# ProPrj_Motorcycle_Controller_2026-08-27_.net
KiCad netlist of a schematic drawn in EasyEDA Pro
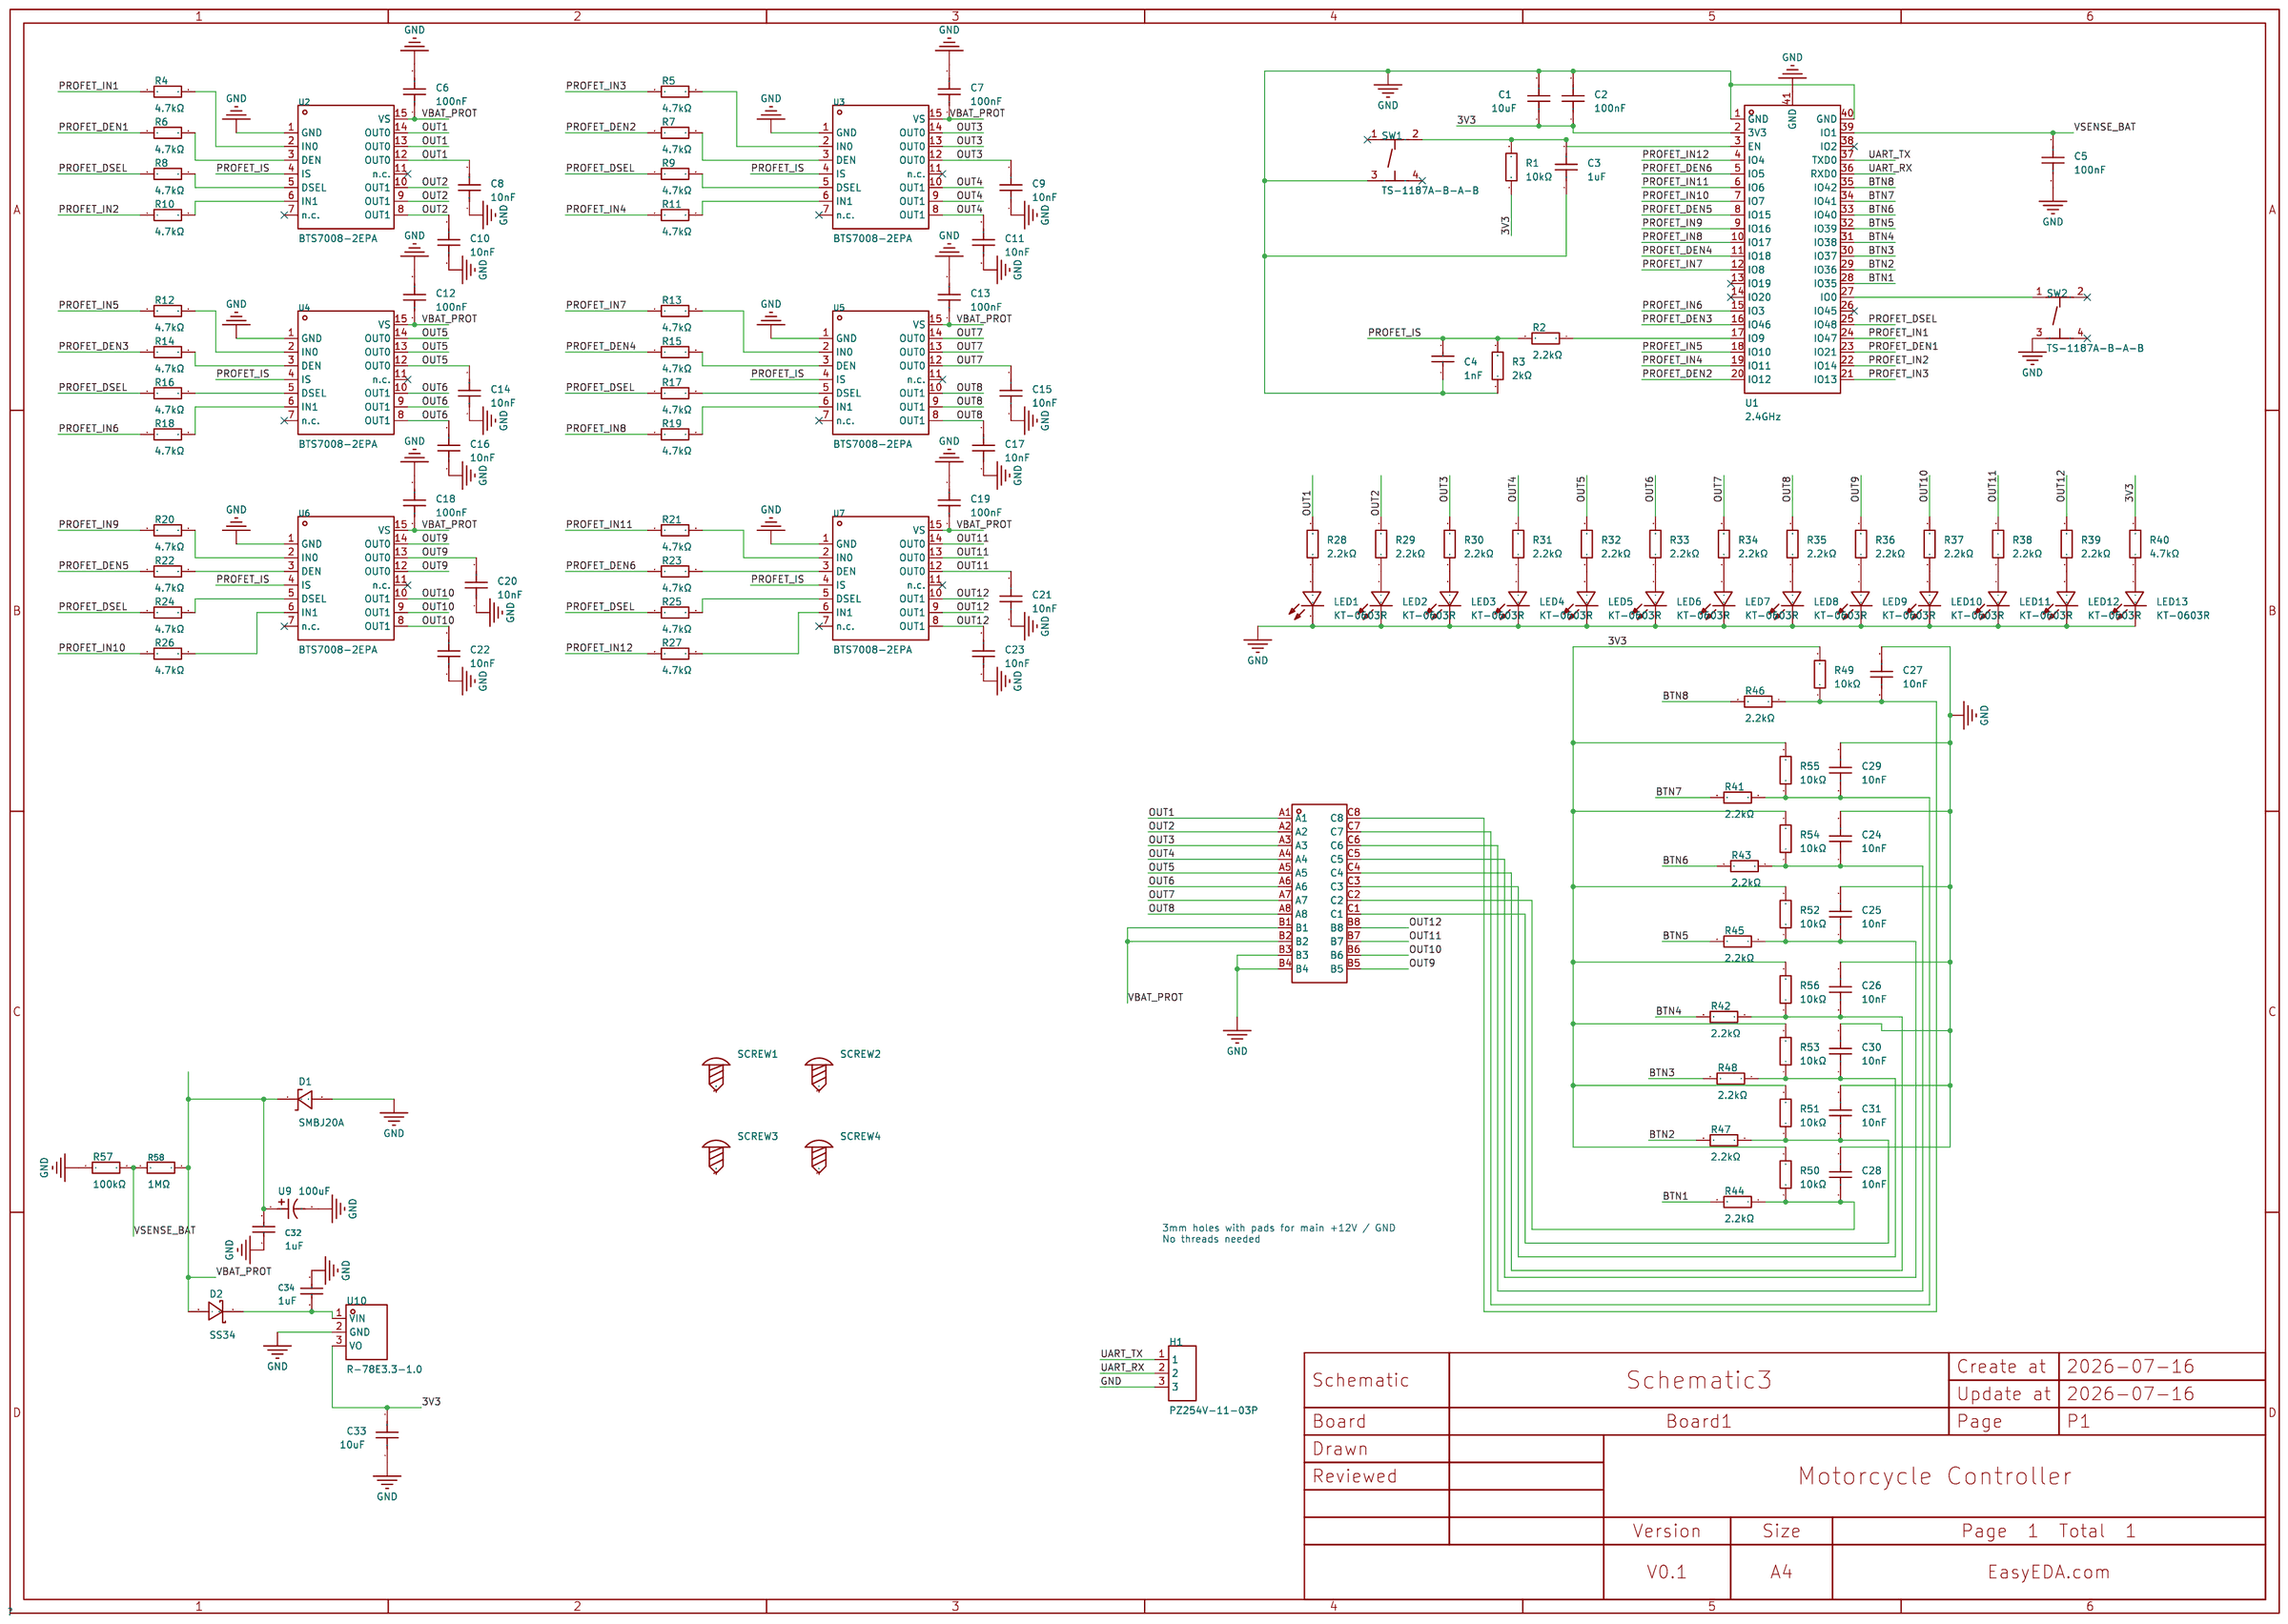
[diagram p0: schematic sheet]

(export (version "E")
  (design (tool "Eeschema 10.0.6"))
  (components
    (comp (ref "C1")
      (value "10uF")
      (footprint "easyedapro:C0603")
      (fields
        (field (name "Manufacturer Part") "CL10A106KP8NNNC")
        (field (name "Manufacturer") "SAMSUNG(三星)")
      )
      (libsource (lib "easyedapro") (part "CL10A106KP8NNNC"))
    )
    (comp (ref "C2")
      (value "100nF")
      (footprint "easyedapro:C0402")
      (fields
        (field (name "Manufacturer Part") "CL05B104KO5NNNC")
        (field (name "Manufacturer") "SAMSUNG(三星)")
      )
      (libsource (lib "easyedapro") (part "CL05B104KO5NNNC"))
    )
    (comp (ref "C3")
      (value "1uF")
      (footprint "easyedapro:C0402")
      (fields
        (field (name "Manufacturer Part") "CL05A105KA5NQNC")
        (field (name "Manufacturer") "SAMSUNG(三星)")
      )
      (libsource (lib "easyedapro") (part "CL05A105KA5NQNC"))
    )
    (comp (ref "C4")
      (value "1nF")
      (footprint "easyedapro:C0402")
      (fields (field (name "Manufacturer Part") "0402B102K500NT") (field (name "Manufacturer") "FH(风华)"))
      (libsource (lib "easyedapro") (part "0402B102K500NT"))
    )
    (comp (ref "C5")
      (value "100nF")
      (footprint "easyedapro:C0402")
      (fields
        (field (name "Manufacturer Part") "CL05B104KO5NNNC")
        (field (name "Manufacturer") "SAMSUNG(三星)")
      )
      (libsource (lib "easyedapro") (part "CL05B104KO5NNNC"))
    )
    (comp (ref "C6")
      (value "100nF")
      (footprint "easyedapro:C0603")
      (fields
        (field (name "Manufacturer Part") "CC0603KRX7R9BB104")
        (field (name "Manufacturer") "YAGEO(国巨)")
      )
      (libsource (lib "easyedapro") (part "CC0603KRX7R9BB104"))
    )
    (comp (ref "C7")
      (value "100nF")
      (footprint "easyedapro:C0603")
      (fields
        (field (name "Manufacturer Part") "CC0603KRX7R9BB104")
        (field (name "Manufacturer") "YAGEO(国巨)")
      )
      (libsource (lib "easyedapro") (part "CC0603KRX7R9BB104"))
    )
    (comp (ref "C8")
      (value "10nF")
      (footprint "easyedapro:C0603")
      (fields (field (name "Manufacturer Part") "0603B103K500NT") (field (name "Manufacturer") "FH(风华)"))
      (libsource (lib "easyedapro") (part "0603B103K500NT"))
    )
    (comp (ref "C9")
      (value "10nF")
      (footprint "easyedapro:C0603")
      (fields (field (name "Manufacturer Part") "0603B103K500NT") (field (name "Manufacturer") "FH(风华)"))
      (libsource (lib "easyedapro") (part "0603B103K500NT"))
    )
    (comp (ref "C10")
      (value "10nF")
      (footprint "easyedapro:C0603")
      (fields (field (name "Manufacturer Part") "0603B103K500NT") (field (name "Manufacturer") "FH(风华)"))
      (libsource (lib "easyedapro") (part "0603B103K500NT"))
    )
    (comp (ref "C11")
      (value "10nF")
      (footprint "easyedapro:C0603")
      (fields (field (name "Manufacturer Part") "0603B103K500NT") (field (name "Manufacturer") "FH(风华)"))
      (libsource (lib "easyedapro") (part "0603B103K500NT"))
    )
    (comp (ref "C12")
      (value "100nF")
      (footprint "easyedapro:C0603")
      (fields
        (field (name "Manufacturer Part") "CC0603KRX7R9BB104")
        (field (name "Manufacturer") "YAGEO(国巨)")
      )
      (libsource (lib "easyedapro") (part "CC0603KRX7R9BB104"))
    )
    (comp (ref "C13")
      (value "100nF")
      (footprint "easyedapro:C0603")
      (fields
        (field (name "Manufacturer Part") "CC0603KRX7R9BB104")
        (field (name "Manufacturer") "YAGEO(国巨)")
      )
      (libsource (lib "easyedapro") (part "CC0603KRX7R9BB104"))
    )
    (comp (ref "C14")
      (value "10nF")
      (footprint "easyedapro:C0603")
      (fields (field (name "Manufacturer Part") "0603B103K500NT") (field (name "Manufacturer") "FH(风华)"))
      (libsource (lib "easyedapro") (part "0603B103K500NT"))
    )
    (comp (ref "C15")
      (value "10nF")
      (footprint "easyedapro:C0603")
      (fields (field (name "Manufacturer Part") "0603B103K500NT") (field (name "Manufacturer") "FH(风华)"))
      (libsource (lib "easyedapro") (part "0603B103K500NT"))
    )
    (comp (ref "C16")
      (value "10nF")
      (footprint "easyedapro:C0603")
      (fields (field (name "Manufacturer Part") "0603B103K500NT") (field (name "Manufacturer") "FH(风华)"))
      (libsource (lib "easyedapro") (part "0603B103K500NT"))
    )
    (comp (ref "C17")
      (value "10nF")
      (footprint "easyedapro:C0603")
      (fields (field (name "Manufacturer Part") "0603B103K500NT") (field (name "Manufacturer") "FH(风华)"))
      (libsource (lib "easyedapro") (part "0603B103K500NT"))
    )
    (comp (ref "C18")
      (value "100nF")
      (footprint "easyedapro:C0603")
      (fields
        (field (name "Manufacturer Part") "CC0603KRX7R9BB104")
        (field (name "Manufacturer") "YAGEO(国巨)")
      )
      (libsource (lib "easyedapro") (part "CC0603KRX7R9BB104"))
    )
    (comp (ref "C19")
      (value "100nF")
      (footprint "easyedapro:C0603")
      (fields
        (field (name "Manufacturer Part") "CC0603KRX7R9BB104")
        (field (name "Manufacturer") "YAGEO(国巨)")
      )
      (libsource (lib "easyedapro") (part "CC0603KRX7R9BB104"))
    )
    (comp (ref "C20")
      (value "10nF")
      (footprint "easyedapro:C0603")
      (fields (field (name "Manufacturer Part") "0603B103K500NT") (field (name "Manufacturer") "FH(风华)"))
      (libsource (lib "easyedapro") (part "0603B103K500NT"))
    )
    (comp (ref "C21")
      (value "10nF")
      (footprint "easyedapro:C0603")
      (fields (field (name "Manufacturer Part") "0603B103K500NT") (field (name "Manufacturer") "FH(风华)"))
      (libsource (lib "easyedapro") (part "0603B103K500NT"))
    )
    (comp (ref "C22")
      (value "10nF")
      (footprint "easyedapro:C0603")
      (fields (field (name "Manufacturer Part") "0603B103K500NT") (field (name "Manufacturer") "FH(风华)"))
      (libsource (lib "easyedapro") (part "0603B103K500NT"))
    )
    (comp (ref "C23")
      (value "10nF")
      (footprint "easyedapro:C0603")
      (fields (field (name "Manufacturer Part") "0603B103K500NT") (field (name "Manufacturer") "FH(风华)"))
      (libsource (lib "easyedapro") (part "0603B103K500NT"))
    )
    (comp (ref "C24")
      (value "10nF")
      (footprint "easyedapro:C0603")
      (fields (field (name "Manufacturer Part") "0603B103K500NT") (field (name "Manufacturer") "FH(风华)"))
      (libsource (lib "easyedapro") (part "0603B103K500NT"))
    )
    (comp (ref "C25")
      (value "10nF")
      (footprint "easyedapro:C0603")
      (fields (field (name "Manufacturer Part") "0603B103K500NT") (field (name "Manufacturer") "FH(风华)"))
      (libsource (lib "easyedapro") (part "0603B103K500NT"))
    )
    (comp (ref "C26")
      (value "10nF")
      (footprint "easyedapro:C0603")
      (fields (field (name "Manufacturer Part") "0603B103K500NT") (field (name "Manufacturer") "FH(风华)"))
      (libsource (lib "easyedapro") (part "0603B103K500NT"))
    )
    (comp (ref "C27")
      (value "10nF")
      (footprint "easyedapro:C0603")
      (fields (field (name "Manufacturer Part") "0603B103K500NT") (field (name "Manufacturer") "FH(风华)"))
      (libsource (lib "easyedapro") (part "0603B103K500NT"))
    )
    (comp (ref "C28")
      (value "10nF")
      (footprint "easyedapro:C0603")
      (fields (field (name "Manufacturer Part") "0603B103K500NT") (field (name "Manufacturer") "FH(风华)"))
      (libsource (lib "easyedapro") (part "0603B103K500NT"))
    )
    (comp (ref "C29")
      (value "10nF")
      (footprint "easyedapro:C0603")
      (fields (field (name "Manufacturer Part") "0603B103K500NT") (field (name "Manufacturer") "FH(风华)"))
      (libsource (lib "easyedapro") (part "0603B103K500NT"))
    )
    (comp (ref "C30")
      (value "10nF")
      (footprint "easyedapro:C0603")
      (fields (field (name "Manufacturer Part") "0603B103K500NT") (field (name "Manufacturer") "FH(风华)"))
      (libsource (lib "easyedapro") (part "0603B103K500NT"))
    )
    (comp (ref "C31")
      (value "10nF")
      (footprint "easyedapro:C0603")
      (fields (field (name "Manufacturer Part") "0603B103K500NT") (field (name "Manufacturer") "FH(风华)"))
      (libsource (lib "easyedapro") (part "0603B103K500NT"))
    )
    (comp (ref "C32")
      (value "1uF")
      (footprint "easyedapro:C0805")
      (fields
        (field (name "Manufacturer Part") "CL21B105KBFNNNE")
        (field (name "Manufacturer") "SAMSUNG(三星)")
      )
      (libsource (lib "easyedapro") (part "CL21B105KBFNNNE"))
    )
    (comp (ref "C33")
      (value "10uF")
      (footprint "easyedapro:C0603")
      (fields
        (field (name "Manufacturer Part") "CL10A106KP8NNNC")
        (field (name "Manufacturer") "SAMSUNG(三星)")
      )
      (libsource (lib "easyedapro") (part "CL10A106KP8NNNC"))
    )
    (comp (ref "C34")
      (value "1uF")
      (footprint "easyedapro:C0805")
      (fields
        (field (name "Manufacturer Part") "CL21B105KBFNNNE")
        (field (name "Manufacturer") "SAMSUNG(三星)")
      )
      (libsource (lib "easyedapro") (part "CL21B105KBFNNNE"))
    )
    (comp (ref "CN3")
      (value "HCCPHPE24BKA90F")
      (footprint "easyedapro:CONN-TH_HCCPHPE24BKA90F")
      (fields (field (name "Manufacturer") "Aptiv(Delphi)"))
      (libsource (lib "easyedapro") (part "HCCPHPE24BKA90F_C5349068"))
    )
    (comp (ref "D1")
      (value "SMBJ20A")
      (footprint "easyedapro:SMB_L4.6-W3.6-LS5.3-RD")
      (fields (field (name "Manufacturer") "MDD(辰达半导体)"))
      (libsource (lib "easyedapro") (part "SMBJ20A_C364296"))
    )
    (comp (ref "D2")
      (value "SS34")
      (footprint "easyedapro:SMA_L4.3-W2.6-LS5.2-RD")
      (fields (field (name "Manufacturer") "MDD(辰达半导体)"))
      (libsource (lib "easyedapro") (part "SS34_C8678"))
    )
    (comp (ref "H1")
      (value "PZ254V-11-03P")
      (footprint "easyedapro:HDR-TH_3P-P2.54-V-M_PZ254V-11-03P")
      (fields (field (name "Manufacturer") "XFCN(兴飞)"))
      (libsource (lib "easyedapro") (part "PZ254V-11-03P_C2937625"))
    )
    (comp (ref "LED1")
      (value "KT-0603R")
      (footprint "easyedapro:LED-SMD_L1.6-W0.8-R-RD")
      (fields (field (name "Manufacturer") "KENTO"))
      (libsource (lib "easyedapro") (part "KT-0603R"))
    )
    (comp (ref "LED2")
      (value "KT-0603R")
      (footprint "easyedapro:LED-SMD_L1.6-W0.8-R-RD")
      (fields (field (name "Manufacturer") "KENTO"))
      (libsource (lib "easyedapro") (part "KT-0603R"))
    )
    (comp (ref "LED3")
      (value "KT-0603R")
      (footprint "easyedapro:LED-SMD_L1.6-W0.8-R-RD")
      (fields (field (name "Manufacturer") "KENTO"))
      (libsource (lib "easyedapro") (part "KT-0603R"))
    )
    (comp (ref "LED4")
      (value "KT-0603R")
      (footprint "easyedapro:LED-SMD_L1.6-W0.8-R-RD")
      (fields (field (name "Manufacturer") "KENTO"))
      (libsource (lib "easyedapro") (part "KT-0603R"))
    )
    (comp (ref "LED5")
      (value "KT-0603R")
      (footprint "easyedapro:LED-SMD_L1.6-W0.8-R-RD")
      (fields (field (name "Manufacturer") "KENTO"))
      (libsource (lib "easyedapro") (part "KT-0603R"))
    )
    (comp (ref "LED6")
      (value "KT-0603R")
      (footprint "easyedapro:LED-SMD_L1.6-W0.8-R-RD")
      (fields (field (name "Manufacturer") "KENTO"))
      (libsource (lib "easyedapro") (part "KT-0603R"))
    )
    (comp (ref "LED7")
      (value "KT-0603R")
      (footprint "easyedapro:LED-SMD_L1.6-W0.8-R-RD")
      (fields (field (name "Manufacturer") "KENTO"))
      (libsource (lib "easyedapro") (part "KT-0603R"))
    )
    (comp (ref "LED8")
      (value "KT-0603R")
      (footprint "easyedapro:LED-SMD_L1.6-W0.8-R-RD")
      (fields (field (name "Manufacturer") "KENTO"))
      (libsource (lib "easyedapro") (part "KT-0603R"))
    )
    (comp (ref "LED9")
      (value "KT-0603R")
      (footprint "easyedapro:LED-SMD_L1.6-W0.8-R-RD")
      (fields (field (name "Manufacturer") "KENTO"))
      (libsource (lib "easyedapro") (part "KT-0603R"))
    )
    (comp (ref "LED10")
      (value "KT-0603R")
      (footprint "easyedapro:LED-SMD_L1.6-W0.8-R-RD")
      (fields (field (name "Manufacturer") "KENTO"))
      (libsource (lib "easyedapro") (part "KT-0603R"))
    )
    (comp (ref "LED11")
      (value "KT-0603R")
      (footprint "easyedapro:LED-SMD_L1.6-W0.8-R-RD")
      (fields (field (name "Manufacturer") "KENTO"))
      (libsource (lib "easyedapro") (part "KT-0603R"))
    )
    (comp (ref "LED12")
      (value "KT-0603R")
      (footprint "easyedapro:LED-SMD_L1.6-W0.8-R-RD")
      (fields (field (name "Manufacturer") "KENTO"))
      (libsource (lib "easyedapro") (part "KT-0603R"))
    )
    (comp (ref "LED13")
      (value "KT-0603R")
      (footprint "easyedapro:LED-SMD_L1.6-W0.8-R-RD")
      (fields (field (name "Manufacturer") "KENTO"))
      (libsource (lib "easyedapro") (part "KT-0603R"))
    )
    (comp (ref "R1")
      (value "10kΩ")
      (footprint "easyedapro:R0402")
      (fields (field (name "Manufacturer Part") "RC0402FR-0710KL") (field (name "Manufacturer") "YAGEO(国巨)"))
      (libsource (lib "easyedapro") (part "RC0402FR-0710KL"))
    )
    (comp (ref "R2")
      (value "2.2kΩ")
      (footprint "easyedapro:R0603")
      (fields
        (field (name "Manufacturer Part") "0603WAF2201T5E")
        (field (name "Manufacturer") "UNI-ROYAL(厚声)")
      )
      (libsource (lib "easyedapro") (part "0603WAF2201T5E"))
    )
    (comp (ref "R3")
      (value "2kΩ")
      (footprint "easyedapro:R0603")
      (fields
        (field (name "Manufacturer Part") "0603WAF2001T5E")
        (field (name "Manufacturer") "UNI-ROYAL(厚声)")
      )
      (libsource (lib "easyedapro") (part "0603WAF2001T5E"))
    )
    (comp (ref "R4")
      (value "4.7kΩ")
      (footprint "easyedapro:R0603")
      (fields
        (field (name "Manufacturer Part") "0603WAF4701T5E")
        (field (name "Manufacturer") "UNI-ROYAL(厚声)")
      )
      (libsource (lib "easyedapro") (part "0603WAF4701T5E"))
    )
    (comp (ref "R5")
      (value "4.7kΩ")
      (footprint "easyedapro:R0603")
      (fields
        (field (name "Manufacturer Part") "0603WAF4701T5E")
        (field (name "Manufacturer") "UNI-ROYAL(厚声)")
      )
      (libsource (lib "easyedapro") (part "0603WAF4701T5E"))
    )
    (comp (ref "R6")
      (value "4.7kΩ")
      (footprint "easyedapro:R0603")
      (fields
        (field (name "Manufacturer Part") "0603WAF4701T5E")
        (field (name "Manufacturer") "UNI-ROYAL(厚声)")
      )
      (libsource (lib "easyedapro") (part "0603WAF4701T5E"))
    )
    (comp (ref "R7")
      (value "4.7kΩ")
      (footprint "easyedapro:R0603")
      (fields
        (field (name "Manufacturer Part") "0603WAF4701T5E")
        (field (name "Manufacturer") "UNI-ROYAL(厚声)")
      )
      (libsource (lib "easyedapro") (part "0603WAF4701T5E"))
    )
    (comp (ref "R8")
      (value "4.7kΩ")
      (footprint "easyedapro:R0603")
      (fields
        (field (name "Manufacturer Part") "0603WAF4701T5E")
        (field (name "Manufacturer") "UNI-ROYAL(厚声)")
      )
      (libsource (lib "easyedapro") (part "0603WAF4701T5E"))
    )
    (comp (ref "R9")
      (value "4.7kΩ")
      (footprint "easyedapro:R0603")
      (fields
        (field (name "Manufacturer Part") "0603WAF4701T5E")
        (field (name "Manufacturer") "UNI-ROYAL(厚声)")
      )
      (libsource (lib "easyedapro") (part "0603WAF4701T5E"))
    )
    (comp (ref "R10")
      (value "4.7kΩ")
      (footprint "easyedapro:R0603")
      (fields
        (field (name "Manufacturer Part") "0603WAF4701T5E")
        (field (name "Manufacturer") "UNI-ROYAL(厚声)")
      )
      (libsource (lib "easyedapro") (part "0603WAF4701T5E"))
    )
    (comp (ref "R11")
      (value "4.7kΩ")
      (footprint "easyedapro:R0603")
      (fields
        (field (name "Manufacturer Part") "0603WAF4701T5E")
        (field (name "Manufacturer") "UNI-ROYAL(厚声)")
      )
      (libsource (lib "easyedapro") (part "0603WAF4701T5E"))
    )
    (comp (ref "R12")
      (value "4.7kΩ")
      (footprint "easyedapro:R0603")
      (fields
        (field (name "Manufacturer Part") "0603WAF4701T5E")
        (field (name "Manufacturer") "UNI-ROYAL(厚声)")
      )
      (libsource (lib "easyedapro") (part "0603WAF4701T5E"))
    )
    (comp (ref "R13")
      (value "4.7kΩ")
      (footprint "easyedapro:R0603")
      (fields
        (field (name "Manufacturer Part") "0603WAF4701T5E")
        (field (name "Manufacturer") "UNI-ROYAL(厚声)")
      )
      (libsource (lib "easyedapro") (part "0603WAF4701T5E"))
    )
    (comp (ref "R14")
      (value "4.7kΩ")
      (footprint "easyedapro:R0603")
      (fields
        (field (name "Manufacturer Part") "0603WAF4701T5E")
        (field (name "Manufacturer") "UNI-ROYAL(厚声)")
      )
      (libsource (lib "easyedapro") (part "0603WAF4701T5E"))
    )
    (comp (ref "R15")
      (value "4.7kΩ")
      (footprint "easyedapro:R0603")
      (fields
        (field (name "Manufacturer Part") "0603WAF4701T5E")
        (field (name "Manufacturer") "UNI-ROYAL(厚声)")
      )
      (libsource (lib "easyedapro") (part "0603WAF4701T5E"))
    )
    (comp (ref "R16")
      (value "4.7kΩ")
      (footprint "easyedapro:R0603")
      (fields
        (field (name "Manufacturer Part") "0603WAF4701T5E")
        (field (name "Manufacturer") "UNI-ROYAL(厚声)")
      )
      (libsource (lib "easyedapro") (part "0603WAF4701T5E"))
    )
    (comp (ref "R17")
      (value "4.7kΩ")
      (footprint "easyedapro:R0603")
      (fields
        (field (name "Manufacturer Part") "0603WAF4701T5E")
        (field (name "Manufacturer") "UNI-ROYAL(厚声)")
      )
      (libsource (lib "easyedapro") (part "0603WAF4701T5E"))
    )
    (comp (ref "R18")
      (value "4.7kΩ")
      (footprint "easyedapro:R0603")
      (fields
        (field (name "Manufacturer Part") "0603WAF4701T5E")
        (field (name "Manufacturer") "UNI-ROYAL(厚声)")
      )
      (libsource (lib "easyedapro") (part "0603WAF4701T5E"))
    )
    (comp (ref "R19")
      (value "4.7kΩ")
      (footprint "easyedapro:R0603")
      (fields
        (field (name "Manufacturer Part") "0603WAF4701T5E")
        (field (name "Manufacturer") "UNI-ROYAL(厚声)")
      )
      (libsource (lib "easyedapro") (part "0603WAF4701T5E"))
    )
    (comp (ref "R20")
      (value "4.7kΩ")
      (footprint "easyedapro:R0603")
      (fields
        (field (name "Manufacturer Part") "0603WAF4701T5E")
        (field (name "Manufacturer") "UNI-ROYAL(厚声)")
      )
      (libsource (lib "easyedapro") (part "0603WAF4701T5E"))
    )
    (comp (ref "R21")
      (value "4.7kΩ")
      (footprint "easyedapro:R0603")
      (fields
        (field (name "Manufacturer Part") "0603WAF4701T5E")
        (field (name "Manufacturer") "UNI-ROYAL(厚声)")
      )
      (libsource (lib "easyedapro") (part "0603WAF4701T5E"))
    )
    (comp (ref "R22")
      (value "4.7kΩ")
      (footprint "easyedapro:R0603")
      (fields
        (field (name "Manufacturer Part") "0603WAF4701T5E")
        (field (name "Manufacturer") "UNI-ROYAL(厚声)")
      )
      (libsource (lib "easyedapro") (part "0603WAF4701T5E"))
    )
    (comp (ref "R23")
      (value "4.7kΩ")
      (footprint "easyedapro:R0603")
      (fields
        (field (name "Manufacturer Part") "0603WAF4701T5E")
        (field (name "Manufacturer") "UNI-ROYAL(厚声)")
      )
      (libsource (lib "easyedapro") (part "0603WAF4701T5E"))
    )
    (comp (ref "R24")
      (value "4.7kΩ")
      (footprint "easyedapro:R0603")
      (fields
        (field (name "Manufacturer Part") "0603WAF4701T5E")
        (field (name "Manufacturer") "UNI-ROYAL(厚声)")
      )
      (libsource (lib "easyedapro") (part "0603WAF4701T5E"))
    )
    (comp (ref "R25")
      (value "4.7kΩ")
      (footprint "easyedapro:R0603")
      (fields
        (field (name "Manufacturer Part") "0603WAF4701T5E")
        (field (name "Manufacturer") "UNI-ROYAL(厚声)")
      )
      (libsource (lib "easyedapro") (part "0603WAF4701T5E"))
    )
    (comp (ref "R26")
      (value "4.7kΩ")
      (footprint "easyedapro:R0603")
      (fields
        (field (name "Manufacturer Part") "0603WAF4701T5E")
        (field (name "Manufacturer") "UNI-ROYAL(厚声)")
      )
      (libsource (lib "easyedapro") (part "0603WAF4701T5E"))
    )
    (comp (ref "R27")
      (value "4.7kΩ")
      (footprint "easyedapro:R0603")
      (fields
        (field (name "Manufacturer Part") "0603WAF4701T5E")
        (field (name "Manufacturer") "UNI-ROYAL(厚声)")
      )
      (libsource (lib "easyedapro") (part "0603WAF4701T5E"))
    )
    (comp (ref "R28")
      (value "2.2kΩ")
      (footprint "easyedapro:R0603")
      (fields
        (field (name "Manufacturer Part") "0603WAF2201T5E")
        (field (name "Manufacturer") "UNI-ROYAL(厚声)")
      )
      (libsource (lib "easyedapro") (part "0603WAF2201T5E"))
    )
    (comp (ref "R29")
      (value "2.2kΩ")
      (footprint "easyedapro:R0603")
      (fields
        (field (name "Manufacturer Part") "0603WAF2201T5E")
        (field (name "Manufacturer") "UNI-ROYAL(厚声)")
      )
      (libsource (lib "easyedapro") (part "0603WAF2201T5E"))
    )
    (comp (ref "R30")
      (value "2.2kΩ")
      (footprint "easyedapro:R0603")
      (fields
        (field (name "Manufacturer Part") "0603WAF2201T5E")
        (field (name "Manufacturer") "UNI-ROYAL(厚声)")
      )
      (libsource (lib "easyedapro") (part "0603WAF2201T5E"))
    )
    (comp (ref "R31")
      (value "2.2kΩ")
      (footprint "easyedapro:R0603")
      (fields
        (field (name "Manufacturer Part") "0603WAF2201T5E")
        (field (name "Manufacturer") "UNI-ROYAL(厚声)")
      )
      (libsource (lib "easyedapro") (part "0603WAF2201T5E"))
    )
    (comp (ref "R32")
      (value "2.2kΩ")
      (footprint "easyedapro:R0603")
      (fields
        (field (name "Manufacturer Part") "0603WAF2201T5E")
        (field (name "Manufacturer") "UNI-ROYAL(厚声)")
      )
      (libsource (lib "easyedapro") (part "0603WAF2201T5E"))
    )
    (comp (ref "R33")
      (value "2.2kΩ")
      (footprint "easyedapro:R0603")
      (fields
        (field (name "Manufacturer Part") "0603WAF2201T5E")
        (field (name "Manufacturer") "UNI-ROYAL(厚声)")
      )
      (libsource (lib "easyedapro") (part "0603WAF2201T5E"))
    )
    (comp (ref "R34")
      (value "2.2kΩ")
      (footprint "easyedapro:R0603")
      (fields
        (field (name "Manufacturer Part") "0603WAF2201T5E")
        (field (name "Manufacturer") "UNI-ROYAL(厚声)")
      )
      (libsource (lib "easyedapro") (part "0603WAF2201T5E"))
    )
    (comp (ref "R35")
      (value "2.2kΩ")
      (footprint "easyedapro:R0603")
      (fields
        (field (name "Manufacturer Part") "0603WAF2201T5E")
        (field (name "Manufacturer") "UNI-ROYAL(厚声)")
      )
      (libsource (lib "easyedapro") (part "0603WAF2201T5E"))
    )
    (comp (ref "R36")
      (value "2.2kΩ")
      (footprint "easyedapro:R0603")
      (fields
        (field (name "Manufacturer Part") "0603WAF2201T5E")
        (field (name "Manufacturer") "UNI-ROYAL(厚声)")
      )
      (libsource (lib "easyedapro") (part "0603WAF2201T5E"))
    )
    (comp (ref "R37")
      (value "2.2kΩ")
      (footprint "easyedapro:R0603")
      (fields
        (field (name "Manufacturer Part") "0603WAF2201T5E")
        (field (name "Manufacturer") "UNI-ROYAL(厚声)")
      )
      (libsource (lib "easyedapro") (part "0603WAF2201T5E"))
    )
    (comp (ref "R38")
      (value "2.2kΩ")
      (footprint "easyedapro:R0603")
      (fields
        (field (name "Manufacturer Part") "0603WAF2201T5E")
        (field (name "Manufacturer") "UNI-ROYAL(厚声)")
      )
      (libsource (lib "easyedapro") (part "0603WAF2201T5E"))
    )
    (comp (ref "R39")
      (value "2.2kΩ")
      (footprint "easyedapro:R0603")
      (fields
        (field (name "Manufacturer Part") "0603WAF2201T5E")
        (field (name "Manufacturer") "UNI-ROYAL(厚声)")
      )
      (libsource (lib "easyedapro") (part "0603WAF2201T5E"))
    )
    (comp (ref "R40")
      (value "4.7kΩ")
      (footprint "easyedapro:R0603")
      (fields
        (field (name "Manufacturer Part") "0603WAF4701T5E")
        (field (name "Manufacturer") "UNI-ROYAL(厚声)")
      )
      (libsource (lib "easyedapro") (part "0603WAF4701T5E"))
    )
    (comp (ref "R41")
      (value "2.2kΩ")
      (footprint "easyedapro:R0603")
      (fields
        (field (name "Manufacturer Part") "0603WAF2201T5E")
        (field (name "Manufacturer") "UNI-ROYAL(厚声)")
      )
      (libsource (lib "easyedapro") (part "0603WAF2201T5E"))
    )
    (comp (ref "R42")
      (value "2.2kΩ")
      (footprint "easyedapro:R0603")
      (fields
        (field (name "Manufacturer Part") "0603WAF2201T5E")
        (field (name "Manufacturer") "UNI-ROYAL(厚声)")
      )
      (libsource (lib "easyedapro") (part "0603WAF2201T5E"))
    )
    (comp (ref "R43")
      (value "2.2kΩ")
      (footprint "easyedapro:R0603")
      (fields
        (field (name "Manufacturer Part") "0603WAF2201T5E")
        (field (name "Manufacturer") "UNI-ROYAL(厚声)")
      )
      (libsource (lib "easyedapro") (part "0603WAF2201T5E"))
    )
    (comp (ref "R44")
      (value "2.2kΩ")
      (footprint "easyedapro:R0603")
      (fields
        (field (name "Manufacturer Part") "0603WAF2201T5E")
        (field (name "Manufacturer") "UNI-ROYAL(厚声)")
      )
      (libsource (lib "easyedapro") (part "0603WAF2201T5E"))
    )
    (comp (ref "R45")
      (value "2.2kΩ")
      (footprint "easyedapro:R0603")
      (fields
        (field (name "Manufacturer Part") "0603WAF2201T5E")
        (field (name "Manufacturer") "UNI-ROYAL(厚声)")
      )
      (libsource (lib "easyedapro") (part "0603WAF2201T5E"))
    )
    (comp (ref "R46")
      (value "2.2kΩ")
      (footprint "easyedapro:R0603")
      (fields
        (field (name "Manufacturer Part") "0603WAF2201T5E")
        (field (name "Manufacturer") "UNI-ROYAL(厚声)")
      )
      (libsource (lib "easyedapro") (part "0603WAF2201T5E"))
    )
    (comp (ref "R47")
      (value "2.2kΩ")
      (footprint "easyedapro:R0603")
      (fields
        (field (name "Manufacturer Part") "0603WAF2201T5E")
        (field (name "Manufacturer") "UNI-ROYAL(厚声)")
      )
      (libsource (lib "easyedapro") (part "0603WAF2201T5E"))
    )
    (comp (ref "R48")
      (value "2.2kΩ")
      (footprint "easyedapro:R0603")
      (fields
        (field (name "Manufacturer Part") "0603WAF2201T5E")
        (field (name "Manufacturer") "UNI-ROYAL(厚声)")
      )
      (libsource (lib "easyedapro") (part "0603WAF2201T5E"))
    )
    (comp (ref "R49")
      (value "10kΩ")
      (footprint "easyedapro:R0402")
      (fields (field (name "Manufacturer Part") "RC0402FR-0710KL") (field (name "Manufacturer") "YAGEO(国巨)"))
      (libsource (lib "easyedapro") (part "RC0402FR-0710KL"))
    )
    (comp (ref "R50")
      (value "10kΩ")
      (footprint "easyedapro:R0402")
      (fields (field (name "Manufacturer Part") "RC0402FR-0710KL") (field (name "Manufacturer") "YAGEO(国巨)"))
      (libsource (lib "easyedapro") (part "RC0402FR-0710KL"))
    )
    (comp (ref "R51")
      (value "10kΩ")
      (footprint "easyedapro:R0402")
      (fields (field (name "Manufacturer Part") "RC0402FR-0710KL") (field (name "Manufacturer") "YAGEO(国巨)"))
      (libsource (lib "easyedapro") (part "RC0402FR-0710KL"))
    )
    (comp (ref "R52")
      (value "10kΩ")
      (footprint "easyedapro:R0402")
      (fields (field (name "Manufacturer Part") "RC0402FR-0710KL") (field (name "Manufacturer") "YAGEO(国巨)"))
      (libsource (lib "easyedapro") (part "RC0402FR-0710KL"))
    )
    (comp (ref "R53")
      (value "10kΩ")
      (footprint "easyedapro:R0402")
      (fields (field (name "Manufacturer Part") "RC0402FR-0710KL") (field (name "Manufacturer") "YAGEO(国巨)"))
      (libsource (lib "easyedapro") (part "RC0402FR-0710KL"))
    )
    (comp (ref "R54")
      (value "10kΩ")
      (footprint "easyedapro:R0402")
      (fields (field (name "Manufacturer Part") "RC0402FR-0710KL") (field (name "Manufacturer") "YAGEO(国巨)"))
      (libsource (lib "easyedapro") (part "RC0402FR-0710KL"))
    )
    (comp (ref "R55")
      (value "10kΩ")
      (footprint "easyedapro:R0402")
      (fields (field (name "Manufacturer Part") "RC0402FR-0710KL") (field (name "Manufacturer") "YAGEO(国巨)"))
      (libsource (lib "easyedapro") (part "RC0402FR-0710KL"))
    )
    (comp (ref "R56")
      (value "10kΩ")
      (footprint "easyedapro:R0402")
      (fields (field (name "Manufacturer Part") "RC0402FR-0710KL") (field (name "Manufacturer") "YAGEO(国巨)"))
      (libsource (lib "easyedapro") (part "RC0402FR-0710KL"))
    )
    (comp (ref "R57")
      (value "100kΩ")
      (footprint "easyedapro:R0603")
      (fields
        (field (name "Manufacturer Part") "0603WAF1003T5E")
        (field (name "Manufacturer") "UNI-ROYAL(厚声)")
      )
      (libsource (lib "easyedapro") (part "0603WAF1003T5E"))
    )
    (comp (ref "R58")
      (value "1MΩ")
      (footprint "easyedapro:R0603")
      (fields
        (field (name "Manufacturer Part") "0603WAF1004T5E")
        (field (name "Manufacturer") "UNI-ROYAL(厚声)")
      )
      (libsource (lib "easyedapro") (part "0603WAF1004T5E"))
    )
    (comp (ref "SCREW1")
      (value "~")
      (footprint "easyedapro:Screw-Hole-M3")
      (libsource (lib "easyedapro") (part "Screw-Hole"))
    )
    (comp (ref "SCREW2")
      (value "~")
      (footprint "easyedapro:Screw-Hole-M3")
      (libsource (lib "easyedapro") (part "Screw-Hole"))
    )
    (comp (ref "SCREW3")
      (value "~")
      (footprint "easyedapro:Screw-Hole-M3")
      (libsource (lib "easyedapro") (part "Screw-Hole"))
    )
    (comp (ref "SCREW4")
      (value "~")
      (footprint "easyedapro:Screw-Hole-M3")
      (libsource (lib "easyedapro") (part "Screw-Hole"))
    )
    (comp (ref "SW1")
      (value "TS-1187A-B-A-B")
      (footprint "easyedapro:SW-SMD_4P-L5.1-W5.1-P3.70-LS6.5-TL_H1.5")
      (fields (field (name "Manufacturer") "XKB Connection(中国星坤)"))
      (libsource (lib "easyedapro") (part "TS-1187A-B-A-B"))
    )
    (comp (ref "SW2")
      (value "TS-1187A-B-A-B")
      (footprint "easyedapro:SW-SMD_4P-L5.1-W5.1-P3.70-LS6.5-TL_H1.5")
      (fields (field (name "Manufacturer") "XKB Connection(中国星坤)"))
      (libsource (lib "easyedapro") (part "TS-1187A-B-A-B"))
    )
    (comp (ref "U1")
      (value "2.4GHz")
      (footprint "easyedapro:WIFIM-SMD_ESP32-S3-WROOM-1-N8")
      (fields
        (field (name "Manufacturer Part") "ESP32-S3-WROOM-1-N4")
        (field (name "Manufacturer") "ESPRESSIF(乐鑫)")
      )
      (libsource (lib "easyedapro") (part "ESP32-S3-WROOM-1-N4"))
    )
    (comp (ref "U2")
      (value "BTS7008-2EPA")
      (footprint "easyedapro:PG-TSDSO-14_L4.9-W3.9-P0.65-LS6.0-BL-EP")
      (fields (field (name "Manufacturer") "Infineon(英飞凌)"))
      (libsource (lib "easyedapro") (part "BTS7008-2EPA"))
    )
    (comp (ref "U3")
      (value "BTS7008-2EPA")
      (footprint "easyedapro:PG-TSDSO-14_L4.9-W3.9-P0.65-LS6.0-BL-EP")
      (fields (field (name "Manufacturer") "Infineon(英飞凌)"))
      (libsource (lib "easyedapro") (part "BTS7008-2EPA"))
    )
    (comp (ref "U4")
      (value "BTS7008-2EPA")
      (footprint "easyedapro:PG-TSDSO-14_L4.9-W3.9-P0.65-LS6.0-BL-EP")
      (fields (field (name "Manufacturer") "Infineon(英飞凌)"))
      (libsource (lib "easyedapro") (part "BTS7008-2EPA"))
    )
    (comp (ref "U5")
      (value "BTS7008-2EPA")
      (footprint "easyedapro:PG-TSDSO-14_L4.9-W3.9-P0.65-LS6.0-BL-EP")
      (fields (field (name "Manufacturer") "Infineon(英飞凌)"))
      (libsource (lib "easyedapro") (part "BTS7008-2EPA"))
    )
    (comp (ref "U6")
      (value "BTS7008-2EPA")
      (footprint "easyedapro:PG-TSDSO-14_L4.9-W3.9-P0.65-LS6.0-BL-EP")
      (fields (field (name "Manufacturer") "Infineon(英飞凌)"))
      (libsource (lib "easyedapro") (part "BTS7008-2EPA"))
    )
    (comp (ref "U7")
      (value "BTS7008-2EPA")
      (footprint "easyedapro:PG-TSDSO-14_L4.9-W3.9-P0.65-LS6.0-BL-EP")
      (fields (field (name "Manufacturer") "Infineon(英飞凌)"))
      (libsource (lib "easyedapro") (part "BTS7008-2EPA"))
    )
    (comp (ref "U9")
      (value "100uF")
      (footprint "easyedapro:CAP-SMD_BD8.0-L8.3-W8.3-LS9.1-FD")
      (fields
        (field (name "Manufacturer Part") "RVT1H101M0810 100UF 50V")
        (field (name "Manufacturer") "DMBJ(振宝佳)")
      )
      (libsource (lib "easyedapro") (part "RVT1H101M0810 100UF 50V"))
    )
    (comp (ref "U10")
      (value "R-78E3.3-1.0")
      (footprint "easyedapro:PWRM-TH_R-78EXX-1.0")
      (fields (field (name "Manufacturer") "YLPTEC(易川)"))
      (libsource (lib "easyedapro") (part "R-78E3.3-1.0"))
    )
  )
  (nets
    (net (code "1") (name "/3V3") (class "Default")
      (node (ref "C1") (pin "1") (pinfunction "1_1") (pintype "unspecified"))
      (node (ref "C2") (pin "1") (pinfunction "1_1") (pintype "unspecified"))
      (node (ref "C33") (pin "2") (pinfunction "2_2") (pintype "unspecified"))
      (node (ref "R1") (pin "1") (pinfunction "1_1") (pintype "input"))
      (node (ref "R40") (pin "2") (pinfunction "2_2") (pintype "input"))
      (node (ref "R49") (pin "2") (pinfunction "2_2") (pintype "input"))
      (node (ref "R50") (pin "2") (pinfunction "2_2") (pintype "input"))
      (node (ref "R51") (pin "2") (pinfunction "2_2") (pintype "input"))
      (node (ref "R52") (pin "2") (pinfunction "2_2") (pintype "input"))
      (node (ref "R53") (pin "2") (pinfunction "2_2") (pintype "input"))
      (node (ref "R54") (pin "2") (pinfunction "2_2") (pintype "input"))
      (node (ref "R55") (pin "2") (pinfunction "2_2") (pintype "input"))
      (node (ref "R56") (pin "2") (pinfunction "2_2") (pintype "input"))
      (node (ref "U1") (pin "2") (pinfunction "3V3_2") (pintype "unspecified"))
      (node (ref "U10") (pin "3") (pinfunction "VO_3") (pintype "unspecified"))
    )
    (net (code "2") (name "/BTN1") (class "Default")
      (node (ref "R44") (pin "2") (pinfunction "2_2") (pintype "input"))
      (node (ref "U1") (pin "28") (pinfunction "IO35_28") (pintype "unspecified"))
    )
    (net (code "3") (name "/BTN2") (class "Default")
      (node (ref "R47") (pin "2") (pinfunction "2_2") (pintype "input"))
      (node (ref "U1") (pin "29") (pinfunction "IO36_29") (pintype "unspecified"))
    )
    (net (code "4") (name "/BTN3") (class "Default")
      (node (ref "R48") (pin "2") (pinfunction "2_2") (pintype "input"))
      (node (ref "U1") (pin "30") (pinfunction "IO37_30") (pintype "unspecified"))
    )
    (net (code "5") (name "/BTN4") (class "Default")
      (node (ref "R42") (pin "2") (pinfunction "2_2") (pintype "input"))
      (node (ref "U1") (pin "31") (pinfunction "IO38_31") (pintype "unspecified"))
    )
    (net (code "6") (name "/BTN5") (class "Default")
      (node (ref "R45") (pin "2") (pinfunction "2_2") (pintype "input"))
      (node (ref "U1") (pin "32") (pinfunction "IO39_32") (pintype "unspecified"))
    )
    (net (code "7") (name "/BTN6") (class "Default")
      (node (ref "R43") (pin "2") (pinfunction "2_2") (pintype "input"))
      (node (ref "U1") (pin "33") (pinfunction "IO40_33") (pintype "unspecified"))
    )
    (net (code "8") (name "/BTN7") (class "Default")
      (node (ref "R41") (pin "2") (pinfunction "2_2") (pintype "input"))
      (node (ref "U1") (pin "34") (pinfunction "IO41_34") (pintype "unspecified"))
    )
    (net (code "9") (name "/BTN8") (class "Default")
      (node (ref "R46") (pin "2") (pinfunction "2_2") (pintype "input"))
      (node (ref "U1") (pin "35") (pinfunction "IO42_35") (pintype "unspecified"))
    )
    (net (code "10") (name "/OUT1") (class "Default")
      (node (ref "C8") (pin "2") (pinfunction "2_2") (pintype "unspecified"))
      (node (ref "CN3") (pin "A1") (pinfunction "A1_A1") (pintype "unspecified"))
      (node (ref "R28") (pin "2") (pinfunction "2_2") (pintype "input"))
      (node (ref "U2") (pin "12") (pinfunction "OUT0_12") (pintype "input"))
      (node (ref "U2") (pin "13") (pinfunction "OUT0_13") (pintype "input"))
      (node (ref "U2") (pin "14") (pinfunction "OUT0_14") (pintype "input"))
    )
    (net (code "11") (name "/OUT2") (class "Default")
      (node (ref "C10") (pin "2") (pinfunction "2_2") (pintype "unspecified"))
      (node (ref "CN3") (pin "A2") (pinfunction "A2_A2") (pintype "unspecified"))
      (node (ref "R29") (pin "2") (pinfunction "2_2") (pintype "input"))
      (node (ref "U2") (pin "10") (pinfunction "OUT1_10") (pintype "input"))
      (node (ref "U2") (pin "8") (pinfunction "OUT1_8") (pintype "input"))
      (node (ref "U2") (pin "9") (pinfunction "OUT1_9") (pintype "input"))
    )
    (net (code "12") (name "/OUT3") (class "Default")
      (node (ref "C9") (pin "2") (pinfunction "2_2") (pintype "unspecified"))
      (node (ref "CN3") (pin "A3") (pinfunction "A3_A3") (pintype "unspecified"))
      (node (ref "R30") (pin "2") (pinfunction "2_2") (pintype "input"))
      (node (ref "U3") (pin "12") (pinfunction "OUT0_12") (pintype "input"))
      (node (ref "U3") (pin "13") (pinfunction "OUT0_13") (pintype "input"))
      (node (ref "U3") (pin "14") (pinfunction "OUT0_14") (pintype "input"))
    )
    (net (code "13") (name "/OUT4") (class "Default")
      (node (ref "C11") (pin "2") (pinfunction "2_2") (pintype "unspecified"))
      (node (ref "CN3") (pin "A4") (pinfunction "A4_A4") (pintype "unspecified"))
      (node (ref "R31") (pin "2") (pinfunction "2_2") (pintype "input"))
      (node (ref "U3") (pin "10") (pinfunction "OUT1_10") (pintype "input"))
      (node (ref "U3") (pin "8") (pinfunction "OUT1_8") (pintype "input"))
      (node (ref "U3") (pin "9") (pinfunction "OUT1_9") (pintype "input"))
    )
    (net (code "14") (name "/OUT5") (class "Default")
      (node (ref "C14") (pin "2") (pinfunction "2_2") (pintype "unspecified"))
      (node (ref "CN3") (pin "A5") (pinfunction "A5_A5") (pintype "unspecified"))
      (node (ref "R32") (pin "2") (pinfunction "2_2") (pintype "input"))
      (node (ref "U4") (pin "12") (pinfunction "OUT0_12") (pintype "input"))
      (node (ref "U4") (pin "13") (pinfunction "OUT0_13") (pintype "input"))
      (node (ref "U4") (pin "14") (pinfunction "OUT0_14") (pintype "input"))
    )
    (net (code "15") (name "/OUT6") (class "Default")
      (node (ref "C16") (pin "2") (pinfunction "2_2") (pintype "unspecified"))
      (node (ref "CN3") (pin "A6") (pinfunction "A6_A6") (pintype "unspecified"))
      (node (ref "R33") (pin "2") (pinfunction "2_2") (pintype "input"))
      (node (ref "U4") (pin "10") (pinfunction "OUT1_10") (pintype "input"))
      (node (ref "U4") (pin "8") (pinfunction "OUT1_8") (pintype "input"))
      (node (ref "U4") (pin "9") (pinfunction "OUT1_9") (pintype "input"))
    )
    (net (code "16") (name "/OUT7") (class "Default")
      (node (ref "C15") (pin "2") (pinfunction "2_2") (pintype "unspecified"))
      (node (ref "CN3") (pin "A7") (pinfunction "A7_A7") (pintype "unspecified"))
      (node (ref "R34") (pin "2") (pinfunction "2_2") (pintype "input"))
      (node (ref "U5") (pin "12") (pinfunction "OUT0_12") (pintype "input"))
      (node (ref "U5") (pin "13") (pinfunction "OUT0_13") (pintype "input"))
      (node (ref "U5") (pin "14") (pinfunction "OUT0_14") (pintype "input"))
    )
    (net (code "17") (name "/OUT8") (class "Default")
      (node (ref "C17") (pin "2") (pinfunction "2_2") (pintype "unspecified"))
      (node (ref "CN3") (pin "A8") (pinfunction "A8_A8") (pintype "unspecified"))
      (node (ref "R35") (pin "2") (pinfunction "2_2") (pintype "input"))
      (node (ref "U5") (pin "10") (pinfunction "OUT1_10") (pintype "input"))
      (node (ref "U5") (pin "8") (pinfunction "OUT1_8") (pintype "input"))
      (node (ref "U5") (pin "9") (pinfunction "OUT1_9") (pintype "input"))
    )
    (net (code "18") (name "/OUT9") (class "Default")
      (node (ref "C20") (pin "2") (pinfunction "2_2") (pintype "unspecified"))
      (node (ref "CN3") (pin "B5") (pinfunction "B5_B5") (pintype "unspecified"))
      (node (ref "R36") (pin "2") (pinfunction "2_2") (pintype "input"))
      (node (ref "U6") (pin "12") (pinfunction "OUT0_12") (pintype "input"))
      (node (ref "U6") (pin "13") (pinfunction "OUT0_13") (pintype "input"))
      (node (ref "U6") (pin "14") (pinfunction "OUT0_14") (pintype "input"))
    )
    (net (code "19") (name "/OUT10") (class "Default")
      (node (ref "C22") (pin "2") (pinfunction "2_2") (pintype "unspecified"))
      (node (ref "CN3") (pin "B6") (pinfunction "B6_B6") (pintype "unspecified"))
      (node (ref "R37") (pin "2") (pinfunction "2_2") (pintype "input"))
      (node (ref "U6") (pin "10") (pinfunction "OUT1_10") (pintype "input"))
      (node (ref "U6") (pin "8") (pinfunction "OUT1_8") (pintype "input"))
      (node (ref "U6") (pin "9") (pinfunction "OUT1_9") (pintype "input"))
    )
    (net (code "20") (name "/OUT11") (class "Default")
      (node (ref "C21") (pin "2") (pinfunction "2_2") (pintype "unspecified"))
      (node (ref "CN3") (pin "B7") (pinfunction "B7_B7") (pintype "unspecified"))
      (node (ref "R38") (pin "2") (pinfunction "2_2") (pintype "input"))
      (node (ref "U7") (pin "12") (pinfunction "OUT0_12") (pintype "input"))
      (node (ref "U7") (pin "13") (pinfunction "OUT0_13") (pintype "input"))
      (node (ref "U7") (pin "14") (pinfunction "OUT0_14") (pintype "input"))
    )
    (net (code "21") (name "/OUT12") (class "Default")
      (node (ref "C23") (pin "2") (pinfunction "2_2") (pintype "unspecified"))
      (node (ref "CN3") (pin "B8") (pinfunction "B8_B8") (pintype "unspecified"))
      (node (ref "R39") (pin "2") (pinfunction "2_2") (pintype "input"))
      (node (ref "U7") (pin "10") (pinfunction "OUT1_10") (pintype "input"))
      (node (ref "U7") (pin "8") (pinfunction "OUT1_8") (pintype "input"))
      (node (ref "U7") (pin "9") (pinfunction "OUT1_9") (pintype "input"))
    )
    (net (code "22") (name "/PROFET_DEN1") (class "Default")
      (node (ref "R6") (pin "1") (pinfunction "1_1") (pintype "input"))
      (node (ref "U1") (pin "23") (pinfunction "IO21_23") (pintype "unspecified"))
    )
    (net (code "23") (name "/PROFET_DEN2") (class "Default")
      (node (ref "R7") (pin "1") (pinfunction "1_1") (pintype "input"))
      (node (ref "U1") (pin "20") (pinfunction "IO12_20") (pintype "unspecified"))
    )
    (net (code "24") (name "/PROFET_DEN3") (class "Default")
      (node (ref "R14") (pin "1") (pinfunction "1_1") (pintype "input"))
      (node (ref "U1") (pin "16") (pinfunction "IO46_16") (pintype "unspecified"))
    )
    (net (code "25") (name "/PROFET_DEN4") (class "Default")
      (node (ref "R15") (pin "1") (pinfunction "1_1") (pintype "input"))
      (node (ref "U1") (pin "11") (pinfunction "IO18_11") (pintype "unspecified"))
    )
    (net (code "26") (name "/PROFET_DEN5") (class "Default")
      (node (ref "R22") (pin "1") (pinfunction "1_1") (pintype "input"))
      (node (ref "U1") (pin "8") (pinfunction "IO15_8") (pintype "unspecified"))
    )
    (net (code "27") (name "/PROFET_DEN6") (class "Default")
      (node (ref "R23") (pin "1") (pinfunction "1_1") (pintype "input"))
      (node (ref "U1") (pin "5") (pinfunction "IO5_5") (pintype "unspecified"))
    )
    (net (code "28") (name "/PROFET_DSEL") (class "Default")
      (node (ref "R16") (pin "1") (pinfunction "1_1") (pintype "input"))
      (node (ref "R17") (pin "1") (pinfunction "1_1") (pintype "input"))
      (node (ref "R24") (pin "1") (pinfunction "1_1") (pintype "input"))
      (node (ref "R25") (pin "1") (pinfunction "1_1") (pintype "input"))
      (node (ref "R8") (pin "1") (pinfunction "1_1") (pintype "input"))
      (node (ref "R9") (pin "1") (pinfunction "1_1") (pintype "input"))
      (node (ref "U1") (pin "25") (pinfunction "IO48_25") (pintype "unspecified"))
    )
    (net (code "29") (name "/PROFET_IN1") (class "Default")
      (node (ref "R4") (pin "1") (pinfunction "1_1") (pintype "input"))
      (node (ref "U1") (pin "24") (pinfunction "IO47_24") (pintype "unspecified"))
    )
    (net (code "30") (name "/PROFET_IN2") (class "Default")
      (node (ref "R10") (pin "1") (pinfunction "1_1") (pintype "input"))
      (node (ref "U1") (pin "22") (pinfunction "IO14_22") (pintype "unspecified"))
    )
    (net (code "31") (name "/PROFET_IN3") (class "Default")
      (node (ref "R5") (pin "1") (pinfunction "1_1") (pintype "input"))
      (node (ref "U1") (pin "21") (pinfunction "IO13_21") (pintype "unspecified"))
    )
    (net (code "32") (name "/PROFET_IN4") (class "Default")
      (node (ref "R11") (pin "1") (pinfunction "1_1") (pintype "input"))
      (node (ref "U1") (pin "19") (pinfunction "IO11_19") (pintype "unspecified"))
    )
    (net (code "33") (name "/PROFET_IN5") (class "Default")
      (node (ref "R12") (pin "1") (pinfunction "1_1") (pintype "input"))
      (node (ref "U1") (pin "18") (pinfunction "IO10_18") (pintype "unspecified"))
    )
    (net (code "34") (name "/PROFET_IN6") (class "Default")
      (node (ref "R18") (pin "1") (pinfunction "1_1") (pintype "input"))
      (node (ref "U1") (pin "15") (pinfunction "IO3_15") (pintype "unspecified"))
    )
    (net (code "35") (name "/PROFET_IN7") (class "Default")
      (node (ref "R13") (pin "1") (pinfunction "1_1") (pintype "input"))
      (node (ref "U1") (pin "12") (pinfunction "IO8_12") (pintype "unspecified"))
    )
    (net (code "36") (name "/PROFET_IN8") (class "Default")
      (node (ref "R19") (pin "1") (pinfunction "1_1") (pintype "input"))
      (node (ref "U1") (pin "10") (pinfunction "IO17_10") (pintype "unspecified"))
    )
    (net (code "37") (name "/PROFET_IN9") (class "Default")
      (node (ref "R20") (pin "1") (pinfunction "1_1") (pintype "input"))
      (node (ref "U1") (pin "9") (pinfunction "IO16_9") (pintype "unspecified"))
    )
    (net (code "38") (name "/PROFET_IN10") (class "Default")
      (node (ref "R26") (pin "1") (pinfunction "1_1") (pintype "input"))
      (node (ref "U1") (pin "7") (pinfunction "IO7_7") (pintype "unspecified"))
    )
    (net (code "39") (name "/PROFET_IN11") (class "Default")
      (node (ref "R21") (pin "1") (pinfunction "1_1") (pintype "input"))
      (node (ref "U1") (pin "6") (pinfunction "IO6_6") (pintype "unspecified"))
    )
    (net (code "40") (name "/PROFET_IN12") (class "Default")
      (node (ref "R27") (pin "1") (pinfunction "1_1") (pintype "input"))
      (node (ref "U1") (pin "4") (pinfunction "IO4_4") (pintype "unspecified"))
    )
    (net (code "41") (name "/PROFET_IS") (class "Default")
      (node (ref "C4") (pin "2") (pinfunction "2_2") (pintype "input"))
      (node (ref "R2") (pin "2") (pinfunction "2_2") (pintype "input"))
      (node (ref "R3") (pin "2") (pinfunction "2_2") (pintype "input"))
      (node (ref "U2") (pin "4") (pinfunction "IS_4") (pintype "input"))
      (node (ref "U3") (pin "4") (pinfunction "IS_4") (pintype "input"))
      (node (ref "U4") (pin "4") (pinfunction "IS_4") (pintype "input"))
      (node (ref "U5") (pin "4") (pinfunction "IS_4") (pintype "input"))
      (node (ref "U6") (pin "4") (pinfunction "IS_4") (pintype "input"))
      (node (ref "U7") (pin "4") (pinfunction "IS_4") (pintype "input"))
    )
    (net (code "42") (name "/UART_RX") (class "Default")
      (node (ref "H1") (pin "2") (pinfunction "2_2") (pintype "unspecified"))
      (node (ref "U1") (pin "36") (pinfunction "RXD0_36") (pintype "unspecified"))
    )
    (net (code "43") (name "/UART_TX") (class "Default")
      (node (ref "H1") (pin "1") (pinfunction "1_1") (pintype "unspecified"))
      (node (ref "U1") (pin "37") (pinfunction "TXD0_37") (pintype "unspecified"))
    )
    (net (code "44") (name "/VBAT_PROT") (class "Default")
      (node (ref "C12") (pin "1") (pinfunction "1_1") (pintype "unspecified"))
      (node (ref "C13") (pin "1") (pinfunction "1_1") (pintype "unspecified"))
      (node (ref "C18") (pin "1") (pinfunction "1_1") (pintype "unspecified"))
      (node (ref "C19") (pin "1") (pinfunction "1_1") (pintype "unspecified"))
      (node (ref "C32") (pin "2") (pinfunction "2_2") (pintype "input"))
      (node (ref "C6") (pin "1") (pinfunction "1_1") (pintype "unspecified"))
      (node (ref "C7") (pin "1") (pinfunction "1_1") (pintype "unspecified"))
      (node (ref "CN3") (pin "B1") (pinfunction "B1_B1") (pintype "unspecified"))
      (node (ref "CN3") (pin "B2") (pinfunction "B2_B2") (pintype "unspecified"))
      (node (ref "D1") (pin "1") (pinfunction "K_1") (pintype "unspecified"))
      (node (ref "D2") (pin "2") (pinfunction "A_2") (pintype "unspecified"))
      (node (ref "R58") (pin "2") (pinfunction "2_2") (pintype "input"))
      (node (ref "U2") (pin "15") (pinfunction "VS_15") (pintype "input"))
      (node (ref "U3") (pin "15") (pinfunction "VS_15") (pintype "input"))
      (node (ref "U4") (pin "15") (pinfunction "VS_15") (pintype "input"))
      (node (ref "U5") (pin "15") (pinfunction "VS_15") (pintype "input"))
      (node (ref "U6") (pin "15") (pinfunction "VS_15") (pintype "input"))
      (node (ref "U7") (pin "15") (pinfunction "VS_15") (pintype "input"))
      (node (ref "U9") (pin "1") (pinfunction "1_1") (pintype "input"))
    )
    (net (code "45") (name "/VSENSE_BAT") (class "Default")
      (node (ref "C5") (pin "2") (pinfunction "2_2") (pintype "unspecified"))
      (node (ref "R57") (pin "2") (pinfunction "2_2") (pintype "input"))
      (node (ref "R58") (pin "1") (pinfunction "1_1") (pintype "input"))
      (node (ref "U1") (pin "39") (pinfunction "IO1_39") (pintype "unspecified"))
    )
    (net (code "46") (name "GND") (class "Default")
      (node (ref "C1") (pin "2") (pinfunction "2_2") (pintype "unspecified"))
      (node (ref "C10") (pin "1") (pinfunction "1_1") (pintype "unspecified"))
      (node (ref "C11") (pin "1") (pinfunction "1_1") (pintype "unspecified"))
      (node (ref "C12") (pin "2") (pinfunction "2_2") (pintype "unspecified"))
      (node (ref "C13") (pin "2") (pinfunction "2_2") (pintype "unspecified"))
      (node (ref "C14") (pin "1") (pinfunction "1_1") (pintype "unspecified"))
      (node (ref "C15") (pin "1") (pinfunction "1_1") (pintype "unspecified"))
      (node (ref "C16") (pin "1") (pinfunction "1_1") (pintype "unspecified"))
      (node (ref "C17") (pin "1") (pinfunction "1_1") (pintype "unspecified"))
      (node (ref "C18") (pin "2") (pinfunction "2_2") (pintype "unspecified"))
      (node (ref "C19") (pin "2") (pinfunction "2_2") (pintype "unspecified"))
      (node (ref "C2") (pin "2") (pinfunction "2_2") (pintype "unspecified"))
      (node (ref "C20") (pin "1") (pinfunction "1_1") (pintype "unspecified"))
      (node (ref "C21") (pin "1") (pinfunction "1_1") (pintype "unspecified"))
      (node (ref "C22") (pin "1") (pinfunction "1_1") (pintype "unspecified"))
      (node (ref "C23") (pin "1") (pinfunction "1_1") (pintype "unspecified"))
      (node (ref "C24") (pin "2") (pinfunction "2_2") (pintype "unspecified"))
      (node (ref "C25") (pin "2") (pinfunction "2_2") (pintype "unspecified"))
      (node (ref "C26") (pin "2") (pinfunction "2_2") (pintype "unspecified"))
      (node (ref "C27") (pin "2") (pinfunction "2_2") (pintype "unspecified"))
      (node (ref "C28") (pin "2") (pinfunction "2_2") (pintype "unspecified"))
      (node (ref "C29") (pin "2") (pinfunction "2_2") (pintype "unspecified"))
      (node (ref "C3") (pin "1") (pinfunction "1_1") (pintype "unspecified"))
      (node (ref "C30") (pin "2") (pinfunction "2_2") (pintype "unspecified"))
      (node (ref "C31") (pin "2") (pinfunction "2_2") (pintype "unspecified"))
      (node (ref "C32") (pin "1") (pinfunction "1_1") (pintype "input"))
      (node (ref "C33") (pin "1") (pinfunction "1_1") (pintype "unspecified"))
      (node (ref "C34") (pin "1") (pinfunction "1_1") (pintype "input"))
      (node (ref "C4") (pin "1") (pinfunction "1_1") (pintype "input"))
      (node (ref "C5") (pin "1") (pinfunction "1_1") (pintype "unspecified"))
      (node (ref "C6") (pin "2") (pinfunction "2_2") (pintype "unspecified"))
      (node (ref "C7") (pin "2") (pinfunction "2_2") (pintype "unspecified"))
      (node (ref "C8") (pin "1") (pinfunction "1_1") (pintype "unspecified"))
      (node (ref "C9") (pin "1") (pinfunction "1_1") (pintype "unspecified"))
      (node (ref "CN3") (pin "B3") (pinfunction "B3_B3") (pintype "unspecified"))
      (node (ref "CN3") (pin "B4") (pinfunction "B4_B4") (pintype "unspecified"))
      (node (ref "D1") (pin "2") (pinfunction "A_2") (pintype "unspecified"))
      (node (ref "H1") (pin "3") (pinfunction "3_3") (pintype "unspecified"))
      (node (ref "LED1") (pin "2") (pinfunction "K_2") (pintype "unspecified"))
      (node (ref "LED10") (pin "2") (pinfunction "K_2") (pintype "unspecified"))
      (node (ref "LED11") (pin "2") (pinfunction "K_2") (pintype "unspecified"))
      (node (ref "LED12") (pin "2") (pinfunction "K_2") (pintype "unspecified"))
      (node (ref "LED13") (pin "2") (pinfunction "K_2") (pintype "unspecified"))
      (node (ref "LED2") (pin "2") (pinfunction "K_2") (pintype "unspecified"))
      (node (ref "LED3") (pin "2") (pinfunction "K_2") (pintype "unspecified"))
      (node (ref "LED4") (pin "2") (pinfunction "K_2") (pintype "unspecified"))
      (node (ref "LED5") (pin "2") (pinfunction "K_2") (pintype "unspecified"))
      (node (ref "LED6") (pin "2") (pinfunction "K_2") (pintype "unspecified"))
      (node (ref "LED7") (pin "2") (pinfunction "K_2") (pintype "unspecified"))
      (node (ref "LED8") (pin "2") (pinfunction "K_2") (pintype "unspecified"))
      (node (ref "LED9") (pin "2") (pinfunction "K_2") (pintype "unspecified"))
      (node (ref "R3") (pin "1") (pinfunction "1_1") (pintype "input"))
      (node (ref "R57") (pin "1") (pinfunction "1_1") (pintype "input"))
      (node (ref "SW1") (pin "3") (pinfunction "C_3") (pintype "unspecified"))
      (node (ref "SW2") (pin "3") (pinfunction "C_3") (pintype "unspecified"))
      (node (ref "U1") (pin "1") (pinfunction "GND_1") (pintype "unspecified"))
      (node (ref "U1") (pin "40") (pinfunction "GND_40") (pintype "unspecified"))
      (node (ref "U1") (pin "41") (pinfunction "GND_41") (pintype "unspecified"))
      (node (ref "U10") (pin "2") (pinfunction "GND_2") (pintype "unspecified"))
      (node (ref "U2") (pin "1") (pinfunction "GND_1") (pintype "input"))
      (node (ref "U3") (pin "1") (pinfunction "GND_1") (pintype "input"))
      (node (ref "U4") (pin "1") (pinfunction "GND_1") (pintype "input"))
      (node (ref "U5") (pin "1") (pinfunction "GND_1") (pintype "input"))
      (node (ref "U6") (pin "1") (pinfunction "GND_1") (pintype "input"))
      (node (ref "U7") (pin "1") (pinfunction "GND_1") (pintype "input"))
      (node (ref "U9") (pin "2") (pinfunction "2_2") (pintype "input"))
    )
    (net (code "47") (name "Net-(C24-Pad1)") (class "Default")
      (node (ref "C24") (pin "1") (pinfunction "1_1") (pintype "unspecified"))
      (node (ref "CN3") (pin "C6") (pinfunction "C6_C6") (pintype "unspecified"))
      (node (ref "R43") (pin "1") (pinfunction "1_1") (pintype "input"))
      (node (ref "R54") (pin "1") (pinfunction "1_1") (pintype "input"))
    )
    (net (code "48") (name "Net-(C25-Pad1)") (class "Default")
      (node (ref "C25") (pin "1") (pinfunction "1_1") (pintype "unspecified"))
      (node (ref "CN3") (pin "C5") (pinfunction "C5_C5") (pintype "unspecified"))
      (node (ref "R45") (pin "1") (pinfunction "1_1") (pintype "input"))
      (node (ref "R52") (pin "1") (pinfunction "1_1") (pintype "input"))
    )
    (net (code "49") (name "Net-(C26-Pad1)") (class "Default")
      (node (ref "C26") (pin "1") (pinfunction "1_1") (pintype "unspecified"))
      (node (ref "CN3") (pin "C4") (pinfunction "C4_C4") (pintype "unspecified"))
      (node (ref "R42") (pin "1") (pinfunction "1_1") (pintype "input"))
      (node (ref "R56") (pin "1") (pinfunction "1_1") (pintype "input"))
    )
    (net (code "50") (name "Net-(C27-Pad1)") (class "Default")
      (node (ref "C27") (pin "1") (pinfunction "1_1") (pintype "unspecified"))
      (node (ref "CN3") (pin "C8") (pinfunction "C8_C8") (pintype "unspecified"))
      (node (ref "R46") (pin "1") (pinfunction "1_1") (pintype "input"))
      (node (ref "R49") (pin "1") (pinfunction "1_1") (pintype "input"))
    )
    (net (code "51") (name "Net-(C28-Pad1)") (class "Default")
      (node (ref "C28") (pin "1") (pinfunction "1_1") (pintype "unspecified"))
      (node (ref "CN3") (pin "C2") (pinfunction "C2_C2") (pintype "unspecified"))
      (node (ref "R44") (pin "1") (pinfunction "1_1") (pintype "input"))
      (node (ref "R50") (pin "1") (pinfunction "1_1") (pintype "input"))
    )
    (net (code "52") (name "Net-(C29-Pad1)") (class "Default")
      (node (ref "C29") (pin "1") (pinfunction "1_1") (pintype "unspecified"))
      (node (ref "CN3") (pin "C7") (pinfunction "C7_C7") (pintype "unspecified"))
      (node (ref "R41") (pin "1") (pinfunction "1_1") (pintype "input"))
      (node (ref "R55") (pin "1") (pinfunction "1_1") (pintype "input"))
    )
    (net (code "53") (name "Net-(C30-Pad1)") (class "Default")
      (node (ref "C30") (pin "1") (pinfunction "1_1") (pintype "unspecified"))
      (node (ref "CN3") (pin "C3") (pinfunction "C3_C3") (pintype "unspecified"))
      (node (ref "R48") (pin "1") (pinfunction "1_1") (pintype "input"))
      (node (ref "R53") (pin "1") (pinfunction "1_1") (pintype "input"))
    )
    (net (code "54") (name "Net-(C31-Pad1)") (class "Default")
      (node (ref "C31") (pin "1") (pinfunction "1_1") (pintype "unspecified"))
      (node (ref "CN3") (pin "C1") (pinfunction "C1_C1") (pintype "unspecified"))
      (node (ref "R47") (pin "1") (pinfunction "1_1") (pintype "input"))
      (node (ref "R51") (pin "1") (pinfunction "1_1") (pintype "input"))
    )
    (net (code "55") (name "Net-(D2-K)") (class "Default")
      (node (ref "C34") (pin "2") (pinfunction "2_2") (pintype "input"))
      (node (ref "D2") (pin "1") (pinfunction "K_1") (pintype "unspecified"))
      (node (ref "U10") (pin "1") (pinfunction "VIN_1") (pintype "unspecified"))
    )
    (net (code "56") (name "Net-(LED1-A)") (class "Default")
      (node (ref "LED1") (pin "1") (pinfunction "A_1") (pintype "unspecified"))
      (node (ref "R28") (pin "1") (pinfunction "1_1") (pintype "input"))
    )
    (net (code "57") (name "Net-(LED2-A)") (class "Default")
      (node (ref "LED2") (pin "1") (pinfunction "A_1") (pintype "unspecified"))
      (node (ref "R29") (pin "1") (pinfunction "1_1") (pintype "input"))
    )
    (net (code "58") (name "Net-(LED3-A)") (class "Default")
      (node (ref "LED3") (pin "1") (pinfunction "A_1") (pintype "unspecified"))
      (node (ref "R30") (pin "1") (pinfunction "1_1") (pintype "input"))
    )
    (net (code "59") (name "Net-(LED4-A)") (class "Default")
      (node (ref "LED4") (pin "1") (pinfunction "A_1") (pintype "unspecified"))
      (node (ref "R31") (pin "1") (pinfunction "1_1") (pintype "input"))
    )
    (net (code "60") (name "Net-(LED5-A)") (class "Default")
      (node (ref "LED5") (pin "1") (pinfunction "A_1") (pintype "unspecified"))
      (node (ref "R32") (pin "1") (pinfunction "1_1") (pintype "input"))
    )
    (net (code "61") (name "Net-(LED6-A)") (class "Default")
      (node (ref "LED6") (pin "1") (pinfunction "A_1") (pintype "unspecified"))
      (node (ref "R33") (pin "1") (pinfunction "1_1") (pintype "input"))
    )
    (net (code "62") (name "Net-(LED7-A)") (class "Default")
      (node (ref "LED7") (pin "1") (pinfunction "A_1") (pintype "unspecified"))
      (node (ref "R34") (pin "1") (pinfunction "1_1") (pintype "input"))
    )
    (net (code "63") (name "Net-(LED8-A)") (class "Default")
      (node (ref "LED8") (pin "1") (pinfunction "A_1") (pintype "unspecified"))
      (node (ref "R35") (pin "1") (pinfunction "1_1") (pintype "input"))
    )
    (net (code "64") (name "Net-(LED9-A)") (class "Default")
      (node (ref "LED9") (pin "1") (pinfunction "A_1") (pintype "unspecified"))
      (node (ref "R36") (pin "1") (pinfunction "1_1") (pintype "input"))
    )
    (net (code "65") (name "Net-(LED10-A)") (class "Default")
      (node (ref "LED10") (pin "1") (pinfunction "A_1") (pintype "unspecified"))
      (node (ref "R37") (pin "1") (pinfunction "1_1") (pintype "input"))
    )
    (net (code "66") (name "Net-(LED11-A)") (class "Default")
      (node (ref "LED11") (pin "1") (pinfunction "A_1") (pintype "unspecified"))
      (node (ref "R38") (pin "1") (pinfunction "1_1") (pintype "input"))
    )
    (net (code "67") (name "Net-(LED12-A)") (class "Default")
      (node (ref "LED12") (pin "1") (pinfunction "A_1") (pintype "unspecified"))
      (node (ref "R39") (pin "1") (pinfunction "1_1") (pintype "input"))
    )
    (net (code "68") (name "Net-(LED13-A)") (class "Default")
      (node (ref "LED13") (pin "1") (pinfunction "A_1") (pintype "unspecified"))
      (node (ref "R40") (pin "1") (pinfunction "1_1") (pintype "input"))
    )
    (net (code "69") (name "Net-(SW1-B)") (class "Default")
      (node (ref "C3") (pin "2") (pinfunction "2_2") (pintype "unspecified"))
      (node (ref "R1") (pin "2") (pinfunction "2_2") (pintype "input"))
      (node (ref "SW1") (pin "2") (pinfunction "B_2") (pintype "unspecified"))
      (node (ref "U1") (pin "3") (pinfunction "EN_3") (pintype "unspecified"))
    )
    (net (code "70") (name "Net-(SW2-A)") (class "Default")
      (node (ref "SW2") (pin "1") (pinfunction "A_1") (pintype "unspecified"))
      (node (ref "U1") (pin "27") (pinfunction "IO0_27") (pintype "unspecified"))
    )
    (net (code "71") (name "Net-(U1-IO9)") (class "Default")
      (node (ref "R2") (pin "1") (pinfunction "1_1") (pintype "input"))
      (node (ref "U1") (pin "17") (pinfunction "IO9_17") (pintype "unspecified"))
    )
    (net (code "72") (name "Net-(U2-DEN)") (class "Default")
      (node (ref "R6") (pin "2") (pinfunction "2_2") (pintype "input"))
      (node (ref "U2") (pin "3") (pinfunction "DEN_3") (pintype "input"))
    )
    (net (code "73") (name "Net-(U2-DSEL)") (class "Default")
      (node (ref "R8") (pin "2") (pinfunction "2_2") (pintype "input"))
      (node (ref "U2") (pin "5") (pinfunction "DSEL_5") (pintype "input"))
    )
    (net (code "74") (name "Net-(U2-IN0)") (class "Default")
      (node (ref "R4") (pin "2") (pinfunction "2_2") (pintype "input"))
      (node (ref "U2") (pin "2") (pinfunction "IN0_2") (pintype "input"))
    )
    (net (code "75") (name "Net-(U2-IN1)") (class "Default")
      (node (ref "R10") (pin "2") (pinfunction "2_2") (pintype "input"))
      (node (ref "U2") (pin "6") (pinfunction "IN1_6") (pintype "input"))
    )
    (net (code "76") (name "Net-(U3-DEN)") (class "Default")
      (node (ref "R7") (pin "2") (pinfunction "2_2") (pintype "input"))
      (node (ref "U3") (pin "3") (pinfunction "DEN_3") (pintype "input"))
    )
    (net (code "77") (name "Net-(U3-DSEL)") (class "Default")
      (node (ref "R9") (pin "2") (pinfunction "2_2") (pintype "input"))
      (node (ref "U3") (pin "5") (pinfunction "DSEL_5") (pintype "input"))
    )
    (net (code "78") (name "Net-(U3-IN0)") (class "Default")
      (node (ref "R5") (pin "2") (pinfunction "2_2") (pintype "input"))
      (node (ref "U3") (pin "2") (pinfunction "IN0_2") (pintype "input"))
    )
    (net (code "79") (name "Net-(U3-IN1)") (class "Default")
      (node (ref "R11") (pin "2") (pinfunction "2_2") (pintype "input"))
      (node (ref "U3") (pin "6") (pinfunction "IN1_6") (pintype "input"))
    )
    (net (code "80") (name "Net-(U4-DEN)") (class "Default")
      (node (ref "R14") (pin "2") (pinfunction "2_2") (pintype "input"))
      (node (ref "U4") (pin "3") (pinfunction "DEN_3") (pintype "input"))
    )
    (net (code "81") (name "Net-(U4-DSEL)") (class "Default")
      (node (ref "R16") (pin "2") (pinfunction "2_2") (pintype "input"))
      (node (ref "U4") (pin "5") (pinfunction "DSEL_5") (pintype "input"))
    )
    (net (code "82") (name "Net-(U4-IN0)") (class "Default")
      (node (ref "R12") (pin "2") (pinfunction "2_2") (pintype "input"))
      (node (ref "U4") (pin "2") (pinfunction "IN0_2") (pintype "input"))
    )
    (net (code "83") (name "Net-(U4-IN1)") (class "Default")
      (node (ref "R18") (pin "2") (pinfunction "2_2") (pintype "input"))
      (node (ref "U4") (pin "6") (pinfunction "IN1_6") (pintype "input"))
    )
    (net (code "84") (name "Net-(U5-DEN)") (class "Default")
      (node (ref "R15") (pin "2") (pinfunction "2_2") (pintype "input"))
      (node (ref "U5") (pin "3") (pinfunction "DEN_3") (pintype "input"))
    )
    (net (code "85") (name "Net-(U5-DSEL)") (class "Default")
      (node (ref "R17") (pin "2") (pinfunction "2_2") (pintype "input"))
      (node (ref "U5") (pin "5") (pinfunction "DSEL_5") (pintype "input"))
    )
    (net (code "86") (name "Net-(U5-IN0)") (class "Default")
      (node (ref "R13") (pin "2") (pinfunction "2_2") (pintype "input"))
      (node (ref "U5") (pin "2") (pinfunction "IN0_2") (pintype "input"))
    )
    (net (code "87") (name "Net-(U5-IN1)") (class "Default")
      (node (ref "R19") (pin "2") (pinfunction "2_2") (pintype "input"))
      (node (ref "U5") (pin "6") (pinfunction "IN1_6") (pintype "input"))
    )
    (net (code "88") (name "Net-(U6-DEN)") (class "Default")
      (node (ref "R22") (pin "2") (pinfunction "2_2") (pintype "input"))
      (node (ref "U6") (pin "3") (pinfunction "DEN_3") (pintype "input"))
    )
    (net (code "89") (name "Net-(U6-DSEL)") (class "Default")
      (node (ref "R24") (pin "2") (pinfunction "2_2") (pintype "input"))
      (node (ref "U6") (pin "5") (pinfunction "DSEL_5") (pintype "input"))
    )
    (net (code "90") (name "Net-(U6-IN0)") (class "Default")
      (node (ref "R20") (pin "2") (pinfunction "2_2") (pintype "input"))
      (node (ref "U6") (pin "2") (pinfunction "IN0_2") (pintype "input"))
    )
    (net (code "91") (name "Net-(U6-IN1)") (class "Default")
      (node (ref "R26") (pin "2") (pinfunction "2_2") (pintype "input"))
      (node (ref "U6") (pin "6") (pinfunction "IN1_6") (pintype "input"))
    )
    (net (code "92") (name "Net-(U7-DEN)") (class "Default")
      (node (ref "R23") (pin "2") (pinfunction "2_2") (pintype "input"))
      (node (ref "U7") (pin "3") (pinfunction "DEN_3") (pintype "input"))
    )
    (net (code "93") (name "Net-(U7-DSEL)") (class "Default")
      (node (ref "R25") (pin "2") (pinfunction "2_2") (pintype "input"))
      (node (ref "U7") (pin "5") (pinfunction "DSEL_5") (pintype "input"))
    )
    (net (code "94") (name "Net-(U7-IN0)") (class "Default")
      (node (ref "R21") (pin "2") (pinfunction "2_2") (pintype "input"))
      (node (ref "U7") (pin "2") (pinfunction "IN0_2") (pintype "input"))
    )
    (net (code "95") (name "Net-(U7-IN1)") (class "Default")
      (node (ref "R27") (pin "2") (pinfunction "2_2") (pintype "input"))
      (node (ref "U7") (pin "6") (pinfunction "IN1_6") (pintype "input"))
    )
    (net (code "96") (name "unconnected-(SCREW1-Pad1)") (class "Default")
      (node (ref "SCREW1") (pin "1") (pinfunction "1_1") (pintype "input"))
    )
    (net (code "97") (name "unconnected-(SCREW2-Pad1)") (class "Default")
      (node (ref "SCREW2") (pin "1") (pinfunction "1_1") (pintype "input"))
    )
    (net (code "98") (name "unconnected-(SCREW3-Pad1)") (class "Default")
      (node (ref "SCREW3") (pin "1") (pinfunction "1_1") (pintype "input"))
    )
    (net (code "99") (name "unconnected-(SCREW4-Pad1)") (class "Default")
      (node (ref "SCREW4") (pin "1") (pinfunction "1_1") (pintype "input"))
    )
    (net (code "100") (name "unconnected-(SW1-A-Pad1)") (class "Default")
      (node (ref "SW1") (pin "1") (pinfunction "A_1") (pintype "unspecified+no_connect"))
    )
    (net (code "101") (name "unconnected-(SW1-D-Pad4)") (class "Default")
      (node (ref "SW1") (pin "4") (pinfunction "D_4") (pintype "unspecified+no_connect"))
    )
    (net (code "102") (name "unconnected-(SW2-B-Pad2)") (class "Default")
      (node (ref "SW2") (pin "2") (pinfunction "B_2") (pintype "unspecified+no_connect"))
    )
    (net (code "103") (name "unconnected-(SW2-D-Pad4)") (class "Default")
      (node (ref "SW2") (pin "4") (pinfunction "D_4") (pintype "unspecified+no_connect"))
    )
    (net (code "104") (name "unconnected-(U1-IO2-Pad38)") (class "Default")
      (node (ref "U1") (pin "38") (pinfunction "IO2_38") (pintype "unspecified+no_connect"))
    )
    (net (code "105") (name "unconnected-(U1-IO19-Pad13)") (class "Default")
      (node (ref "U1") (pin "13") (pinfunction "IO19_13") (pintype "unspecified+no_connect"))
    )
    (net (code "106") (name "unconnected-(U1-IO20-Pad14)") (class "Default")
      (node (ref "U1") (pin "14") (pinfunction "IO20_14") (pintype "unspecified+no_connect"))
    )
    (net (code "107") (name "unconnected-(U1-IO45-Pad26)") (class "Default")
      (node (ref "U1") (pin "26") (pinfunction "IO45_26") (pintype "unspecified+no_connect"))
    )
    (net (code "108") (name "unconnected-(U2-n.c.-Pad7)") (class "Default")
      (node (ref "U2") (pin "7") (pinfunction "n.c._7") (pintype "input+no_connect"))
    )
    (net (code "109") (name "unconnected-(U2-n.c.-Pad11)") (class "Default")
      (node (ref "U2") (pin "11") (pinfunction "n.c._11") (pintype "input+no_connect"))
    )
    (net (code "110") (name "unconnected-(U3-n.c.-Pad7)") (class "Default")
      (node (ref "U3") (pin "7") (pinfunction "n.c._7") (pintype "input+no_connect"))
    )
    (net (code "111") (name "unconnected-(U3-n.c.-Pad11)") (class "Default")
      (node (ref "U3") (pin "11") (pinfunction "n.c._11") (pintype "input+no_connect"))
    )
    (net (code "112") (name "unconnected-(U4-n.c.-Pad7)") (class "Default")
      (node (ref "U4") (pin "7") (pinfunction "n.c._7") (pintype "input+no_connect"))
    )
    (net (code "113") (name "unconnected-(U4-n.c.-Pad11)") (class "Default")
      (node (ref "U4") (pin "11") (pinfunction "n.c._11") (pintype "input+no_connect"))
    )
    (net (code "114") (name "unconnected-(U5-n.c.-Pad7)") (class "Default")
      (node (ref "U5") (pin "7") (pinfunction "n.c._7") (pintype "input+no_connect"))
    )
    (net (code "115") (name "unconnected-(U5-n.c.-Pad11)") (class "Default")
      (node (ref "U5") (pin "11") (pinfunction "n.c._11") (pintype "input+no_connect"))
    )
    (net (code "116") (name "unconnected-(U6-n.c.-Pad7)") (class "Default")
      (node (ref "U6") (pin "7") (pinfunction "n.c._7") (pintype "input+no_connect"))
    )
    (net (code "117") (name "unconnected-(U6-n.c.-Pad11)") (class "Default")
      (node (ref "U6") (pin "11") (pinfunction "n.c._11") (pintype "input+no_connect"))
    )
    (net (code "118") (name "unconnected-(U7-n.c.-Pad7)") (class "Default")
      (node (ref "U7") (pin "7") (pinfunction "n.c._7") (pintype "input+no_connect"))
    )
    (net (code "119") (name "unconnected-(U7-n.c.-Pad11)") (class "Default")
      (node (ref "U7") (pin "11") (pinfunction "n.c._11") (pintype "input+no_connect"))
    )
  )
)
